# rx.net
KiCad netlist of a schematic drawn in EAGLE
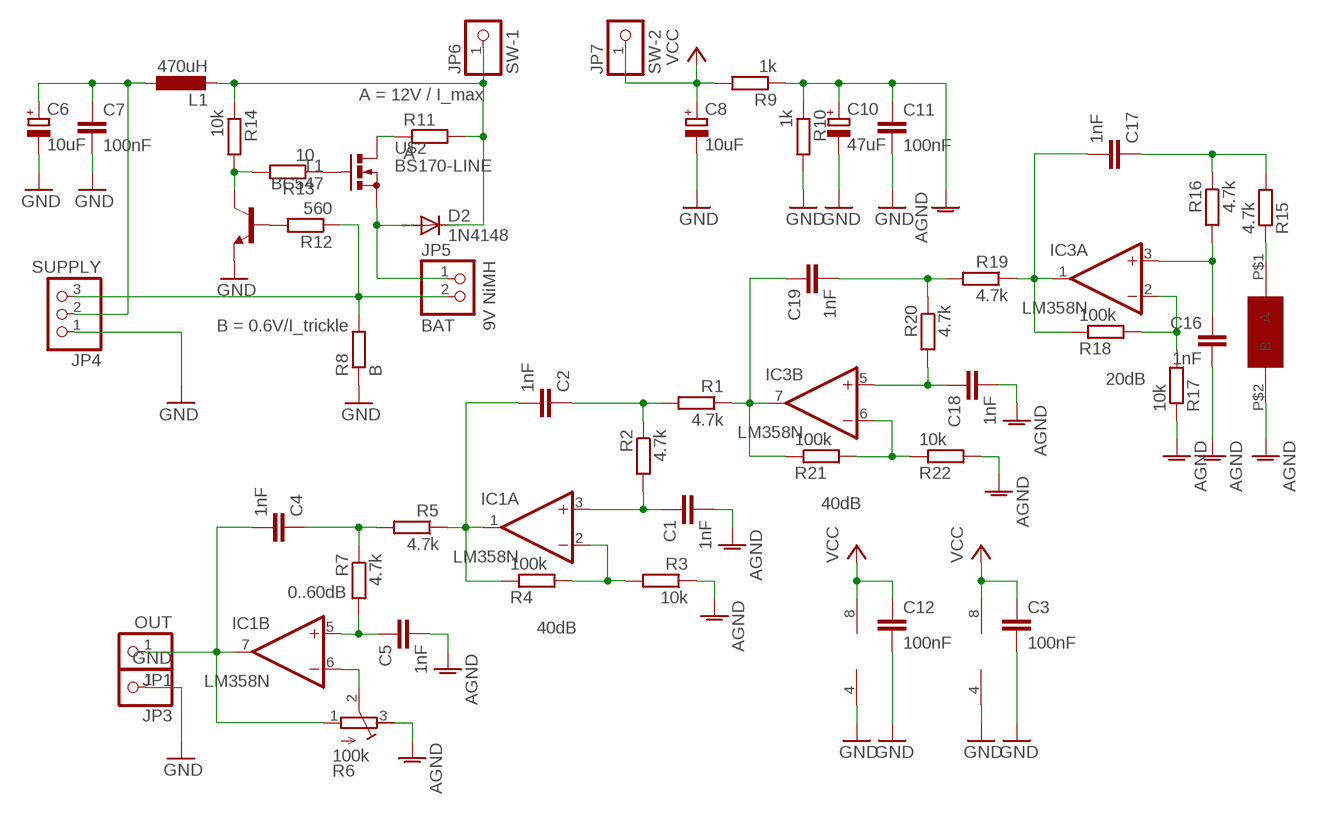
[diagram p0: schematic, sheet 1]

(export (version "E")
  (design (tool "Eeschema 10.0.6"))
  (components
    (comp (ref "C1")
      (value "1nF")
      (footprint "eagle-import:C075-032X103")
      (libsource (lib "eagle-import") (part "C-EU075-032X103"))
    )
    (comp (ref "C2")
      (value "1nF")
      (footprint "eagle-import:C025-025X050")
      (libsource (lib "eagle-import") (part "C-EU025-025X050"))
    )
    (comp (ref "C3")
      (value "100nF")
      (footprint "eagle-import:C025-025X050")
      (libsource (lib "eagle-import") (part "C-EU025-025X050"))
    )
    (comp (ref "C4")
      (value "1nF")
      (footprint "eagle-import:C025-025X050")
      (libsource (lib "eagle-import") (part "C-EU025-025X050"))
    )
    (comp (ref "C5")
      (value "1nF")
      (footprint "eagle-import:C025-025X050")
      (libsource (lib "eagle-import") (part "C-EU025-025X050"))
    )
    (comp (ref "C6")
      (value "10uF")
      (footprint "eagle-import:E2,5-6")
      (libsource (lib "eagle-import") (part "CPOL-EUE2.5-6"))
    )
    (comp (ref "C7")
      (value "100nF")
      (footprint "eagle-import:C025-025X050")
      (libsource (lib "eagle-import") (part "C-EU025-025X050"))
    )
    (comp (ref "C8")
      (value "10uF")
      (footprint "eagle-import:E2,5-6")
      (libsource (lib "eagle-import") (part "CPOL-EUE2.5-6"))
    )
    (comp (ref "C10")
      (value "47uF")
      (footprint "eagle-import:E2,5-6")
      (libsource (lib "eagle-import") (part "CPOL-EUE2.5-6"))
    )
    (comp (ref "C11")
      (value "100nF")
      (footprint "eagle-import:C025-025X050")
      (libsource (lib "eagle-import") (part "C-EU025-025X050"))
    )
    (comp (ref "C12")
      (value "100nF")
      (footprint "eagle-import:C025-025X050")
      (libsource (lib "eagle-import") (part "C-EU025-025X050"))
    )
    (comp (ref "C16")
      (value "1nF")
      (footprint "eagle-import:C025-025X050")
      (libsource (lib "eagle-import") (part "C-EU025-025X050"))
    )
    (comp (ref "C17")
      (value "1nF")
      (footprint "eagle-import:C025-025X050")
      (libsource (lib "eagle-import") (part "C-EU025-025X050"))
    )
    (comp (ref "C18")
      (value "1nF")
      (footprint "eagle-import:C075-032X103")
      (libsource (lib "eagle-import") (part "C-EU075-032X103"))
    )
    (comp (ref "C19")
      (value "1nF")
      (footprint "eagle-import:C025-025X050")
      (libsource (lib "eagle-import") (part "C-EU025-025X050"))
    )
    (comp (ref "D2")
      (value "1N4148")
      (footprint "eagle-import:D-2.5")
      (libsource (lib "eagle-import") (part "DIODE-D-2.5"))
    )
    (comp (ref "IC1")
      (value "LM358N")
      (footprint "eagle-import:DIL08")
      (libsource (lib "eagle-import") (part "LM358N"))
    )
    (comp (ref "IC3")
      (value "LM358N")
      (footprint "eagle-import:DIL08")
      (libsource (lib "eagle-import") (part "LM358N"))
    )
    (comp (ref "JP1")
      (value "OUT")
      (footprint "eagle-import:1X01")
      (libsource (lib "eagle-import") (part "PINHD-1X1"))
    )
    (comp (ref "JP3")
      (value "GND")
      (footprint "eagle-import:1X01")
      (libsource (lib "eagle-import") (part "PINHD-1X1"))
    )
    (comp (ref "JP4")
      (value "SUPPLY")
      (footprint "eagle-import:1X03")
      (libsource (lib "eagle-import") (part "PINHD-1X3"))
    )
    (comp (ref "JP5")
      (value "BAT")
      (footprint "eagle-import:1X02")
      (libsource (lib "eagle-import") (part "PINHD-1X2"))
    )
    (comp (ref "JP6")
      (value "SW-1")
      (footprint "eagle-import:1X01")
      (libsource (lib "eagle-import") (part "PINHD-1X1"))
    )
    (comp (ref "JP7")
      (value "SW-2")
      (footprint "eagle-import:1X01")
      (libsource (lib "eagle-import") (part "PINHD-1X1"))
    )
    (comp (ref "L1")
      (value "470uH")
      (footprint "eagle-import:0204_5")
      (libsource (lib "eagle-import") (part "L-EU0204/5"))
    )
    (comp (ref "R1")
      (value "4.7k")
      (footprint "eagle-import:0207_10")
      (libsource (lib "eagle-import") (part "R-EU_0207/10"))
    )
    (comp (ref "R2")
      (value "4.7k")
      (footprint "eagle-import:0207_10")
      (libsource (lib "eagle-import") (part "R-EU_0207/10"))
    )
    (comp (ref "R3")
      (value "10k")
      (footprint "eagle-import:0207_10")
      (libsource (lib "eagle-import") (part "R-EU_0207/10"))
    )
    (comp (ref "R4")
      (value "100k")
      (footprint "eagle-import:0204V")
      (libsource (lib "eagle-import") (part "R-EU_0204/2V"))
    )
    (comp (ref "R5")
      (value "4.7k")
      (footprint "eagle-import:0204_7")
      (libsource (lib "eagle-import") (part "R-EU_0204/7"))
    )
    (comp (ref "R6")
      (value "100k")
      (footprint "eagle-import:RTRIM64W")
      (libsource (lib "eagle-import") (part "R-TRIMM64W"))
    )
    (comp (ref "R7")
      (value "4.7k")
      (footprint "eagle-import:0204_7")
      (libsource (lib "eagle-import") (part "R-EU_0204/7"))
    )
    (comp (ref "R8")
      (value "B")
      (footprint "eagle-import:0204_5")
      (libsource (lib "eagle-import") (part "R-EU_0204/5"))
    )
    (comp (ref "R9")
      (value "1k")
      (footprint "eagle-import:0204_5")
      (libsource (lib "eagle-import") (part "R-EU_0204/5"))
    )
    (comp (ref "R10")
      (value "1k")
      (footprint "eagle-import:0204V")
      (libsource (lib "eagle-import") (part "R-EU_0204/2V"))
    )
    (comp (ref "R11")
      (value "A")
      (footprint "eagle-import:0204_5")
      (libsource (lib "eagle-import") (part "R-EU_0204/5"))
    )
    (comp (ref "R12")
      (value "560")
      (footprint "eagle-import:0204_7")
      (libsource (lib "eagle-import") (part "R-EU_0204/7"))
    )
    (comp (ref "R13")
      (value "10")
      (footprint "eagle-import:0204V")
      (libsource (lib "eagle-import") (part "R-EU_0204/2V"))
    )
    (comp (ref "R14")
      (value "10k")
      (footprint "eagle-import:0204V")
      (libsource (lib "eagle-import") (part "R-EU_0204/2V"))
    )
    (comp (ref "R15")
      (value "4.7k")
      (footprint "eagle-import:0204_5")
      (libsource (lib "eagle-import") (part "R-EU_0204/5"))
    )
    (comp (ref "R16")
      (value "4.7k")
      (footprint "eagle-import:0204_5")
      (libsource (lib "eagle-import") (part "R-EU_0204/5"))
    )
    (comp (ref "R17")
      (value "10k")
      (footprint "eagle-import:0204_5")
      (libsource (lib "eagle-import") (part "R-EU_0204/5"))
    )
    (comp (ref "R18")
      (value "100k")
      (footprint "eagle-import:0204V")
      (libsource (lib "eagle-import") (part "R-EU_0204/2V"))
    )
    (comp (ref "R19")
      (value "4.7k")
      (footprint "eagle-import:0207_10")
      (libsource (lib "eagle-import") (part "R-EU_0207/10"))
    )
    (comp (ref "R20")
      (value "4.7k")
      (footprint "eagle-import:0204_7")
      (libsource (lib "eagle-import") (part "R-EU_0204/7"))
    )
    (comp (ref "R21")
      (value "100k")
      (footprint "eagle-import:0204V")
      (libsource (lib "eagle-import") (part "R-EU_0204/2V"))
    )
    (comp (ref "R22")
      (value "10k")
      (footprint "eagle-import:0204_5")
      (libsource (lib "eagle-import") (part "R-EU_0204/5"))
    )
    (comp (ref "T1")
      (value "BC547")
      (footprint "eagle-import:TO92-CBE")
      (libsource (lib "eagle-import") (part "-NPN-TO92-CBE"))
    )
    (comp (ref "U$1")
      (value "FERITTE")
      (footprint "eagle-import:FERRITE")
      (libsource (lib "eagle-import") (part "FERITTE"))
    )
    (comp (ref "U$2")
      (value "BS170-LINE")
      (footprint "eagle-import:TO92-LINE")
      (libsource (lib "eagle-import") (part "BS170-LINE"))
    )
  )
  (nets
    (net (code "1") (name "AGND") (class "Default")
      (node (ref "C1") (pin "2") (pinfunction "2_2") (pintype "passive"))
      (node (ref "C10") (pin "+") (pinfunction "+_+") (pintype "passive"))
      (node (ref "C11") (pin "1") (pinfunction "1_1") (pintype "passive"))
      (node (ref "C16") (pin "2") (pinfunction "2_2") (pintype "passive"))
      (node (ref "C18") (pin "2") (pinfunction "2_2") (pintype "passive"))
      (node (ref "C5") (pin "2") (pinfunction "2_2") (pintype "passive"))
      (node (ref "R10") (pin "1") (pinfunction "1_1") (pintype "passive"))
      (node (ref "R17") (pin "1") (pinfunction "1_1") (pintype "passive"))
      (node (ref "R22") (pin "2") (pinfunction "2_2") (pintype "passive"))
      (node (ref "R3") (pin "1") (pinfunction "1_1") (pintype "passive"))
      (node (ref "R6") (pin "3") (pinfunction "E_3") (pintype "passive"))
      (node (ref "R9") (pin "1") (pinfunction "1_1") (pintype "passive"))
      (node (ref "U$1") (pin "P$2") (pinfunction "B_P$2") (pintype "bidirectional"))
    )
    (net (code "2") (name "GND") (class "Default")
      (node (ref "C10") (pin "-") (pinfunction "-_-") (pintype "passive"))
      (node (ref "C11") (pin "2") (pinfunction "2_2") (pintype "passive"))
      (node (ref "C12") (pin "2") (pinfunction "2_2") (pintype "passive"))
      (node (ref "C3") (pin "2") (pinfunction "2_2") (pintype "passive"))
      (node (ref "C6") (pin "-") (pinfunction "-_-") (pintype "passive"))
      (node (ref "C7") (pin "2") (pinfunction "2_2") (pintype "passive"))
      (node (ref "C8") (pin "-") (pinfunction "-_-") (pintype "passive"))
      (node (ref "IC1") (pin "4") (pinfunction "V-_4") (pintype "power_in"))
      (node (ref "IC3") (pin "4") (pinfunction "V-_4") (pintype "power_in"))
      (node (ref "JP3") (pin "1") (pinfunction "1_1") (pintype "passive"))
      (node (ref "JP4") (pin "1") (pinfunction "1_1") (pintype "passive"))
      (node (ref "R10") (pin "2") (pinfunction "2_2") (pintype "passive"))
      (node (ref "R8") (pin "1") (pinfunction "1_1") (pintype "passive"))
      (node (ref "T1") (pin "E") (pinfunction "E_E") (pintype "passive"))
    )
    (net (code "3") (name "Net-(C2-Pad1)") (class "Default")
      (node (ref "C2") (pin "1") (pinfunction "1_1") (pintype "passive"))
      (node (ref "R1") (pin "2") (pinfunction "2_2") (pintype "passive"))
      (node (ref "R2") (pin "1") (pinfunction "1_1") (pintype "passive"))
    )
    (net (code "4") (name "Net-(C4-Pad1)") (class "Default")
      (node (ref "C4") (pin "1") (pinfunction "1_1") (pintype "passive"))
      (node (ref "R5") (pin "2") (pinfunction "2_2") (pintype "passive"))
      (node (ref "R7") (pin "1") (pinfunction "1_1") (pintype "passive"))
    )
    (net (code "5") (name "Net-(C6-Pad+)") (class "Default")
      (node (ref "C6") (pin "+") (pinfunction "+_+") (pintype "passive"))
      (node (ref "C7") (pin "1") (pinfunction "1_1") (pintype "passive"))
      (node (ref "JP4") (pin "2") (pinfunction "2_2") (pintype "passive"))
      (node (ref "L1") (pin "1") (pinfunction "1_1") (pintype "passive"))
    )
    (net (code "6") (name "Net-(C17-Pad1)") (class "Default")
      (node (ref "C17") (pin "1") (pinfunction "1_1") (pintype "passive"))
      (node (ref "R15") (pin "2") (pinfunction "2_2") (pintype "passive"))
      (node (ref "R16") (pin "1") (pinfunction "1_1") (pintype "passive"))
    )
    (net (code "7") (name "Net-(C19-Pad2)") (class "Default")
      (node (ref "C19") (pin "2") (pinfunction "2_2") (pintype "passive"))
      (node (ref "R19") (pin "2") (pinfunction "2_2") (pintype "passive"))
      (node (ref "R20") (pin "1") (pinfunction "1_1") (pintype "passive"))
    )
    (net (code "8") (name "Net-(D2-PadC)") (class "Default")
      (node (ref "D2") (pin "C") (pinfunction "C_C") (pintype "passive"))
      (node (ref "JP6") (pin "1") (pinfunction "1_1") (pintype "passive"))
      (node (ref "L1") (pin "2") (pinfunction "2_2") (pintype "passive"))
      (node (ref "R11") (pin "2") (pinfunction "2_2") (pintype "passive"))
      (node (ref "R14") (pin "1") (pinfunction "1_1") (pintype "passive"))
    )
    (net (code "9") (name "Net-(IC1A-+IN)") (class "Default")
      (node (ref "C1") (pin "1") (pinfunction "1_1") (pintype "passive"))
      (node (ref "IC1") (pin "3") (pinfunction "+IN_3") (pintype "input"))
      (node (ref "R2") (pin "2") (pinfunction "2_2") (pintype "passive"))
    )
    (net (code "10") (name "Net-(IC1A--IN)") (class "Default")
      (node (ref "IC1") (pin "2") (pinfunction "-IN_2") (pintype "input"))
      (node (ref "R3") (pin "2") (pinfunction "2_2") (pintype "passive"))
      (node (ref "R4") (pin "2") (pinfunction "2_2") (pintype "passive"))
    )
    (net (code "11") (name "Net-(IC1A-OUT)") (class "Default")
      (node (ref "C2") (pin "2") (pinfunction "2_2") (pintype "passive"))
      (node (ref "IC1") (pin "1") (pinfunction "OUT_1") (pintype "output"))
      (node (ref "R4") (pin "1") (pinfunction "1_1") (pintype "passive"))
      (node (ref "R5") (pin "1") (pinfunction "1_1") (pintype "passive"))
    )
    (net (code "12") (name "Net-(IC1B-+IN)") (class "Default")
      (node (ref "C5") (pin "1") (pinfunction "1_1") (pintype "passive"))
      (node (ref "IC1") (pin "5") (pinfunction "+IN_5") (pintype "input"))
      (node (ref "R7") (pin "2") (pinfunction "2_2") (pintype "passive"))
    )
    (net (code "13") (name "Net-(IC1B--IN)") (class "Default")
      (node (ref "IC1") (pin "6") (pinfunction "-IN_6") (pintype "input"))
      (node (ref "R6") (pin "2") (pinfunction "S_2") (pintype "passive"))
    )
    (net (code "14") (name "Net-(IC1B-OUT)") (class "Default")
      (node (ref "C4") (pin "2") (pinfunction "2_2") (pintype "passive"))
      (node (ref "IC1") (pin "7") (pinfunction "OUT_7") (pintype "output"))
      (node (ref "JP1") (pin "1") (pinfunction "1_1") (pintype "passive"))
      (node (ref "R6") (pin "1") (pinfunction "A_1") (pintype "passive"))
    )
    (net (code "15") (name "Net-(IC3A-+IN)") (class "Default")
      (node (ref "C16") (pin "1") (pinfunction "1_1") (pintype "passive"))
      (node (ref "IC3") (pin "3") (pinfunction "+IN_3") (pintype "input"))
      (node (ref "R16") (pin "2") (pinfunction "2_2") (pintype "passive"))
    )
    (net (code "16") (name "Net-(IC3A--IN)") (class "Default")
      (node (ref "IC3") (pin "2") (pinfunction "-IN_2") (pintype "input"))
      (node (ref "R17") (pin "2") (pinfunction "2_2") (pintype "passive"))
      (node (ref "R18") (pin "2") (pinfunction "2_2") (pintype "passive"))
    )
    (net (code "17") (name "Net-(IC3A-OUT)") (class "Default")
      (node (ref "C17") (pin "2") (pinfunction "2_2") (pintype "passive"))
      (node (ref "IC3") (pin "1") (pinfunction "OUT_1") (pintype "output"))
      (node (ref "R18") (pin "1") (pinfunction "1_1") (pintype "passive"))
      (node (ref "R19") (pin "1") (pinfunction "1_1") (pintype "passive"))
    )
    (net (code "18") (name "Net-(IC3B-+IN)") (class "Default")
      (node (ref "C18") (pin "1") (pinfunction "1_1") (pintype "passive"))
      (node (ref "IC3") (pin "5") (pinfunction "+IN_5") (pintype "input"))
      (node (ref "R20") (pin "2") (pinfunction "2_2") (pintype "passive"))
    )
    (net (code "19") (name "Net-(IC3B--IN)") (class "Default")
      (node (ref "IC3") (pin "6") (pinfunction "-IN_6") (pintype "input"))
      (node (ref "R21") (pin "2") (pinfunction "2_2") (pintype "passive"))
      (node (ref "R22") (pin "1") (pinfunction "1_1") (pintype "passive"))
    )
    (net (code "20") (name "Net-(IC3B-OUT)") (class "Default")
      (node (ref "C19") (pin "1") (pinfunction "1_1") (pintype "passive"))
      (node (ref "IC3") (pin "7") (pinfunction "OUT_7") (pintype "output"))
      (node (ref "R1") (pin "1") (pinfunction "1_1") (pintype "passive"))
      (node (ref "R21") (pin "1") (pinfunction "1_1") (pintype "passive"))
    )
    (net (code "21") (name "Net-(JP4-Pad3)") (class "Default")
      (node (ref "JP4") (pin "3") (pinfunction "3_3") (pintype "passive"))
      (node (ref "JP5") (pin "2") (pinfunction "2_2") (pintype "passive"))
      (node (ref "R12") (pin "1") (pinfunction "1_1") (pintype "passive"))
      (node (ref "R8") (pin "2") (pinfunction "2_2") (pintype "passive"))
    )
    (net (code "22") (name "Net-(R12-Pad2)") (class "Default")
      (node (ref "R12") (pin "2") (pinfunction "2_2") (pintype "passive"))
      (node (ref "T1") (pin "B") (pinfunction "B_B") (pintype "passive"))
    )
    (net (code "23") (name "Net-(R13-Pad2)") (class "Default")
      (node (ref "R13") (pin "2") (pinfunction "2_2") (pintype "passive"))
      (node (ref "R14") (pin "2") (pinfunction "2_2") (pintype "passive"))
      (node (ref "T1") (pin "C") (pinfunction "C_C") (pintype "passive"))
    )
    (net (code "24") (name "Net-(U$1-A)") (class "Default")
      (node (ref "R15") (pin "1") (pinfunction "1_1") (pintype "passive"))
      (node (ref "U$1") (pin "P$1") (pinfunction "A_P$1") (pintype "bidirectional"))
    )
    (net (code "25") (name "Net-(U$2-D)") (class "Default")
      (node (ref "R11") (pin "1") (pinfunction "1_1") (pintype "passive"))
      (node (ref "U$2") (pin "3") (pinfunction "D_3") (pintype "passive"))
    )
    (net (code "26") (name "Net-(U$2-G)") (class "Default")
      (node (ref "R13") (pin "1") (pinfunction "1_1") (pintype "passive"))
      (node (ref "U$2") (pin "2") (pinfunction "G_2") (pintype "passive"))
    )
    (net (code "27") (name "Net-(U$2-S)") (class "Default")
      (node (ref "D2") (pin "A") (pinfunction "A_A") (pintype "passive"))
      (node (ref "JP5") (pin "1") (pinfunction "1_1") (pintype "passive"))
      (node (ref "U$2") (pin "1") (pinfunction "S_1") (pintype "passive"))
    )
    (net (code "28") (name "VCC") (class "Default")
      (node (ref "C12") (pin "1") (pinfunction "1_1") (pintype "passive"))
      (node (ref "C3") (pin "1") (pinfunction "1_1") (pintype "passive"))
      (node (ref "C8") (pin "+") (pinfunction "+_+") (pintype "passive"))
      (node (ref "IC1") (pin "8") (pinfunction "V+_8") (pintype "power_in"))
      (node (ref "IC3") (pin "8") (pinfunction "V+_8") (pintype "power_in"))
      (node (ref "JP7") (pin "1") (pinfunction "1_1") (pintype "passive"))
      (node (ref "R9") (pin "2") (pinfunction "2_2") (pintype "passive"))
    )
  )
)
